# ADC-RDC-PHY.net
KiCad netlist of a schematic drawn in Altium Designer
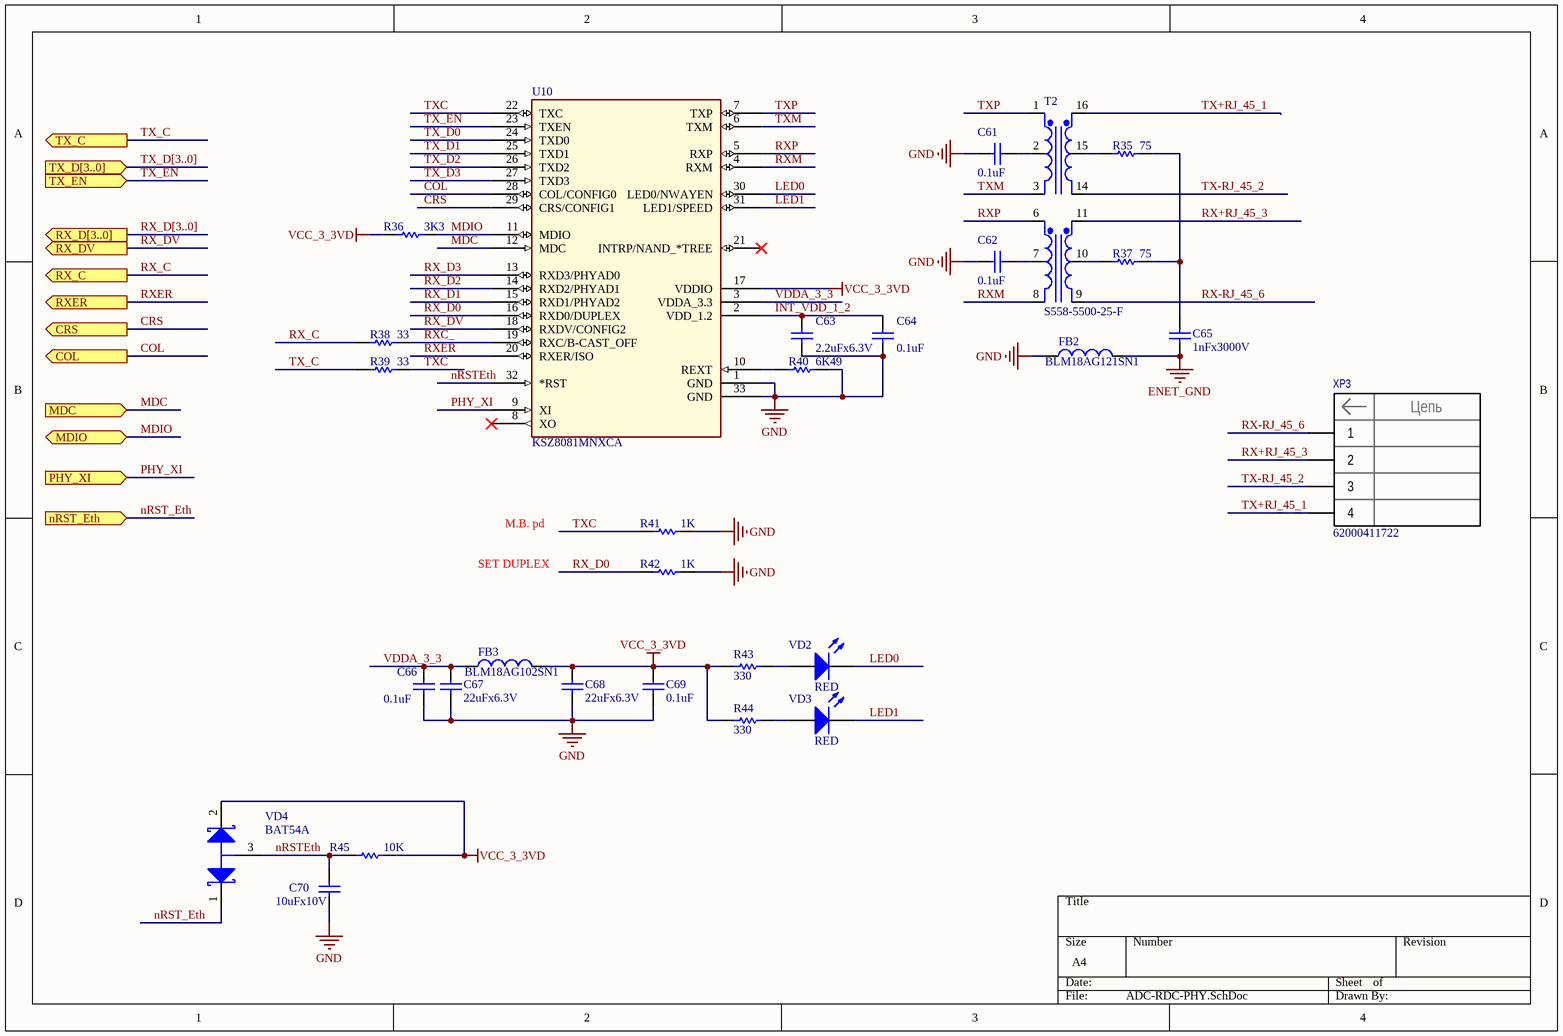
[diagram p0: ADC-RDC-PHY.SchDoc]

(export (version "E")
  (design (tool "Eeschema 10.0.6"))
  (components
    (comp (ref "C61")
      (value "0.1uF")
      (footprint "C0603")
      (description "Capacitor, 2pin")
      (libsource (lib "GC500EM2") (part "Cap"))
    )
    (comp (ref "C62")
      (value "0.1uF")
      (footprint "C0603")
      (description "Capacitor, 2pin")
      (libsource (lib "GC500EM2") (part "Cap"))
    )
    (comp (ref "C63")
      (value "2.2uFx6.3V")
      (footprint "C0603")
      (description "Capacitor, 2pin")
      (libsource (lib "GC500EM2") (part "Cap"))
    )
    (comp (ref "C64")
      (value "0.1uF")
      (footprint "C0603")
      (description "Capacitor, 2pin")
      (libsource (lib "GC500EM2") (part "Cap"))
    )
    (comp (ref "C65")
      (value "1nFx3000V")
      (footprint "C1808")
      (description "Capacitor, 2pin")
      (libsource (lib "GC500EM2") (part "Cap"))
    )
    (comp (ref "C66")
      (value "0.1uF")
      (footprint "C0603")
      (description "Capacitor, 2pin")
      (libsource (lib "GC500EM2") (part "Cap"))
    )
    (comp (ref "C67")
      (value "22uFx6.3V")
      (footprint "C0805")
      (description "Capacitor, 2pin")
      (libsource (lib "GC500EM2") (part "Cap"))
    )
    (comp (ref "C68")
      (value "22uFx6.3V")
      (footprint "C0805")
      (description "Capacitor, 2pin")
      (libsource (lib "GC500EM2") (part "Cap"))
    )
    (comp (ref "C69")
      (value "0.1uF")
      (footprint "C0603")
      (description "Capacitor, 2pin")
      (libsource (lib "GC500EM2") (part "Cap"))
    )
    (comp (ref "C70")
      (value "10uFx10V")
      (footprint "C0805")
      (description "Capacitor, 2pin")
      (libsource (lib "GC500EM2") (part "Cap"))
    )
    (comp (ref "FB2")
      (value "BLM18AG121SN1")
      (footprint "R0603")
      (description "Inductor, 2pin")
      (libsource (lib "GC500EM2") (part "Inductor"))
    )
    (comp (ref "FB3")
      (value "BLM18AG102SN1")
      (footprint "R0603")
      (description "Inductor, 2pin")
      (libsource (lib "GC500EM2") (part "Inductor"))
    )
    (comp (ref "R35")
      (value "75")
      (footprint "R0603")
      (description "Resistor, 2pin")
      (libsource (lib "GC500EM2") (part "RES"))
    )
    (comp (ref "R36")
      (value "3K3")
      (footprint "R0603")
      (description "Resistor, 2pin")
      (libsource (lib "GC500EM2") (part "RES"))
    )
    (comp (ref "R37")
      (value "75")
      (footprint "R0603")
      (description "Resistor, 2pin")
      (libsource (lib "GC500EM2") (part "RES"))
    )
    (comp (ref "R38")
      (value "33")
      (footprint "R0603")
      (description "Resistor, 2pin")
      (libsource (lib "GC500EM2") (part "RES"))
    )
    (comp (ref "R39")
      (value "33")
      (footprint "R0603")
      (description "Resistor, 2pin")
      (libsource (lib "GC500EM2") (part "RES"))
    )
    (comp (ref "R40")
      (value "6K49")
      (footprint "R0603")
      (description "Resistor, 2pin")
      (libsource (lib "GC500EM2") (part "RES"))
    )
    (comp (ref "R41")
      (value "1K")
      (footprint "R0603")
      (description "Resistor, 2pin")
      (libsource (lib "GC500EM2") (part "RES"))
    )
    (comp (ref "R42")
      (value "1K")
      (footprint "R0603")
      (description "Resistor, 2pin")
      (libsource (lib "GC500EM2") (part "RES"))
    )
    (comp (ref "R43")
      (value "330")
      (footprint "R0603")
      (description "Resistor, 2pin")
      (libsource (lib "GC500EM2") (part "RES"))
    )
    (comp (ref "R44")
      (value "330")
      (footprint "R0603")
      (description "Resistor, 2pin")
      (libsource (lib "GC500EM2") (part "RES"))
    )
    (comp (ref "R45")
      (value "10K")
      (footprint "R0603")
      (description "Resistor, 2pin")
      (libsource (lib "GC500EM2") (part "RES"))
    )
    (comp (ref "T2")
      (value "S558-5500-25-F")
      (footprint "N5")
      (description "Center-Tapped Transformer (Ideal)")
      (libsource (lib "GC500EM2") (part "TG110-E050N5"))
    )
    (comp (ref "U10")
      (value "KSZ8081MNXCA")
      (footprint "QFN32_L")
      (description "10BASE-T/100BASE-TX Physical Layer Transceiver")
      (libsource (lib "GC500EM2") (part "KSZ8081MNXCA"))
    )
    (comp (ref "VD2")
      (value "RED")
      (footprint "D0805")
      (description "Typical GaAs LED")
      (libsource (lib "GC500EM2") (part "LED"))
    )
    (comp (ref "VD3")
      (value "RED")
      (footprint "D0805")
      (description "Typical GaAs LED")
      (libsource (lib "GC500EM2") (part "LED"))
    )
    (comp (ref "VD4")
      (value "BAT54A")
      (footprint "SOT-23")
      (description "Schottky Barrier Double Diode")
      (libsource (lib "GC500EM2") (part "BAT54A"))
    )
    (comp (ref "XP3")
      (value "plug_62000411722_WR-WTB_4pin_horiz")
      (footprint "conP_WR-WTB_62000411722-4pin_P2000_100x76x48_L")
      (description "2.00mm Male Vertical Shrouded Header WR-WTB")
      (fields
        (field (name "COMPONENT_NAME") "62000411722")
        (field (name "MANUFACTURER") "\"Wurth Elektronik\"")
      )
      (libsource (lib "Electromechanics") (part "plug_62000411722_WR-WTB_4pin_horiz"))
    )
  )
  (nets
    (net (code "1") (name "/COL") (class "Default")
      (node (ref "U10") (pin "28") (pinfunction "COL/CONFIG0_28") (pintype "bidirectional"))
    )
    (net (code "2") (name "/CRS") (class "Default")
      (node (ref "U10") (pin "29") (pinfunction "CRS/CONFIG1_29") (pintype "bidirectional"))
    )
    (net (code "3") (name "/INT_VDD_1_2") (class "Default")
      (node (ref "C63") (pin "1") (pinfunction "1_1") (pintype "passive"))
      (node (ref "C64") (pin "2") (pinfunction "2_2") (pintype "passive"))
      (node (ref "U10") (pin "2") (pinfunction "VDD_1.2_2") (pintype "power_in"))
    )
    (net (code "4") (name "/LED0") (class "Default")
      (node (ref "U10") (pin "30") (pinfunction "LED0/NWAYEN_30") (pintype "bidirectional"))
      (node (ref "VD2") (pin "2") (pinfunction "K_2") (pintype "passive"))
    )
    (net (code "5") (name "/LED1") (class "Default")
      (node (ref "U10") (pin "31") (pinfunction "LED1/SPEED_31") (pintype "bidirectional"))
      (node (ref "VD3") (pin "2") (pinfunction "K_2") (pintype "passive"))
    )
    (net (code "6") (name "/MDC") (class "Default")
      (node (ref "U10") (pin "12") (pinfunction "MDC_12") (pintype "input"))
    )
    (net (code "7") (name "/MDIO") (class "Default")
      (node (ref "R36") (pin "2") (pinfunction "2_2") (pintype "passive"))
      (node (ref "U10") (pin "11") (pinfunction "MDIO_11") (pintype "bidirectional"))
    )
    (net (code "8") (name "/PHY_XI") (class "Default")
      (node (ref "U10") (pin "9") (pinfunction "XI_9") (pintype "input"))
    )
    (net (code "9") (name "/RX+RJ_45_3") (class "Default")
      (node (ref "T2") (pin "11") (pinfunction "Pri2+_11") (pintype "passive"))
      (node (ref "XP3") (pin "2") (pinfunction "2_2") (pintype "passive"))
    )
    (net (code "10") (name "/RX-RJ_45_6") (class "Default")
      (node (ref "T2") (pin "9") (pinfunction "Pri2-_9") (pintype "passive"))
      (node (ref "XP3") (pin "1") (pinfunction "1_1") (pintype "passive"))
    )
    (net (code "11") (name "/RXC_") (class "Default")
      (node (ref "R38") (pin "2") (pinfunction "2_2") (pintype "passive"))
      (node (ref "U10") (pin "19") (pinfunction "RXC/B-CAST_OFF_19") (pintype "bidirectional"))
    )
    (net (code "12") (name "/RXER") (class "Default")
      (node (ref "U10") (pin "20") (pinfunction "RXER/ISO_20") (pintype "bidirectional"))
    )
    (net (code "13") (name "/RXM") (class "Default")
      (node (ref "T2") (pin "8") (pinfunction "Sec2-_8") (pintype "passive"))
      (node (ref "U10") (pin "4") (pinfunction "RXM_4") (pintype "bidirectional"))
    )
    (net (code "14") (name "/RXP") (class "Default")
      (node (ref "T2") (pin "6") (pinfunction "Sec2+_6") (pintype "passive"))
      (node (ref "U10") (pin "5") (pinfunction "RXP_5") (pintype "bidirectional"))
    )
    (net (code "15") (name "/RX_C") (class "Default")
      (node (ref "R38") (pin "1") (pinfunction "1_1") (pintype "passive"))
    )
    (net (code "16") (name "/RX_D0") (class "Default")
      (node (ref "R42") (pin "1") (pinfunction "1_1") (pintype "passive"))
      (node (ref "U10") (pin "16") (pinfunction "RXD0/DUPLEX_16") (pintype "bidirectional"))
    )
    (net (code "17") (name "/RX_D1") (class "Default")
      (node (ref "U10") (pin "15") (pinfunction "RXD1/PHYAD2_15") (pintype "bidirectional"))
    )
    (net (code "18") (name "/RX_D2") (class "Default")
      (node (ref "U10") (pin "14") (pinfunction "RXD2/PHYAD1_14") (pintype "bidirectional"))
    )
    (net (code "19") (name "/RX_D3") (class "Default")
      (node (ref "U10") (pin "13") (pinfunction "RXD3/PHYAD0_13") (pintype "bidirectional"))
    )
    (net (code "20") (name "/RX_DV") (class "Default")
      (node (ref "U10") (pin "18") (pinfunction "RXDV/CONFIG2_18") (pintype "bidirectional"))
    )
    (net (code "22") (name "/TX+RJ_45_1") (class "Default")
      (node (ref "T2") (pin "16") (pinfunction "Pri1+_16") (pintype "passive"))
      (node (ref "XP3") (pin "4") (pinfunction "4_4") (pintype "passive"))
    )
    (net (code "23") (name "/TX-RJ_45_2") (class "Default")
      (node (ref "T2") (pin "14") (pinfunction "Pri1-_14") (pintype "passive"))
      (node (ref "XP3") (pin "3") (pinfunction "3_3") (pintype "passive"))
    )
    (net (code "24") (name "/TXC") (class "Default")
      (node (ref "R39") (pin "2") (pinfunction "2_2") (pintype "passive"))
      (node (ref "R41") (pin "1") (pinfunction "1_1") (pintype "passive"))
      (node (ref "U10") (pin "22") (pinfunction "TXC_22") (pintype "bidirectional"))
    )
    (net (code "25") (name "/TXM") (class "Default")
      (node (ref "T2") (pin "3") (pinfunction "Sec1-_3") (pintype "passive"))
      (node (ref "U10") (pin "6") (pinfunction "TXM_6") (pintype "bidirectional"))
    )
    (net (code "26") (name "/TXP") (class "Default")
      (node (ref "T2") (pin "1") (pinfunction "Sec1+_1") (pintype "passive"))
      (node (ref "U10") (pin "7") (pinfunction "TXP_7") (pintype "bidirectional"))
    )
    (net (code "27") (name "/TX_C") (class "Default")
      (node (ref "R39") (pin "1") (pinfunction "1_1") (pintype "passive"))
    )
    (net (code "28") (name "/TX_D0") (class "Default")
      (node (ref "U10") (pin "24") (pinfunction "TXD0_24") (pintype "input"))
    )
    (net (code "29") (name "/TX_D1") (class "Default")
      (node (ref "U10") (pin "25") (pinfunction "TXD1_25") (pintype "input"))
    )
    (net (code "30") (name "/TX_D2") (class "Default")
      (node (ref "U10") (pin "26") (pinfunction "TXD2_26") (pintype "input"))
    )
    (net (code "31") (name "/TX_D3") (class "Default")
      (node (ref "U10") (pin "27") (pinfunction "TXD3_27") (pintype "input"))
    )
    (net (code "33") (name "/TX_EN") (class "Default")
      (node (ref "U10") (pin "23") (pinfunction "TXEN_23") (pintype "input"))
    )
    (net (code "34") (name "/VDDA_3_3") (class "Default")
      (node (ref "C66") (pin "2") (pinfunction "2_2") (pintype "passive"))
      (node (ref "C67") (pin "2") (pinfunction "2_2") (pintype "passive"))
      (node (ref "FB3") (pin "2") (pinfunction "2_2") (pintype "passive"))
      (node (ref "U10") (pin "3") (pinfunction "VDDA_3.3_3") (pintype "power_in"))
    )
    (net (code "35") (name "/nRSTEth") (class "Default")
      (node (ref "C70") (pin "1") (pinfunction "1_1") (pintype "passive"))
      (node (ref "R45") (pin "1") (pinfunction "1_1") (pintype "passive"))
      (node (ref "U10") (pin "32") (pinfunction "*RST_32") (pintype "input"))
      (node (ref "VD4") (pin "3") (pinfunction "K_3") (pintype "passive"))
    )
    (net (code "36") (name "/nRST_Eth") (class "Default")
      (node (ref "VD4") (pin "1") (pinfunction "A1_1") (pintype "passive"))
    )
    (net (code "37") (name "ENET_GND") (class "Default")
      (node (ref "C65") (pin "2") (pinfunction "2_2") (pintype "passive"))
      (node (ref "FB2") (pin "1") (pinfunction "1_1") (pintype "passive"))
    )
    (net (code "38") (name "GND") (class "Default")
      (node (ref "C61") (pin "2") (pinfunction "2_2") (pintype "passive"))
      (node (ref "C62") (pin "2") (pinfunction "2_2") (pintype "passive"))
      (node (ref "C63") (pin "2") (pinfunction "2_2") (pintype "passive"))
      (node (ref "C64") (pin "1") (pinfunction "1_1") (pintype "passive"))
      (node (ref "C66") (pin "1") (pinfunction "1_1") (pintype "passive"))
      (node (ref "C67") (pin "1") (pinfunction "1_1") (pintype "passive"))
      (node (ref "C68") (pin "1") (pinfunction "1_1") (pintype "passive"))
      (node (ref "C69") (pin "1") (pinfunction "1_1") (pintype "passive"))
      (node (ref "C70") (pin "2") (pinfunction "2_2") (pintype "passive"))
      (node (ref "FB2") (pin "2") (pinfunction "2_2") (pintype "passive"))
      (node (ref "R40") (pin "2") (pinfunction "2_2") (pintype "passive"))
      (node (ref "R41") (pin "2") (pinfunction "2_2") (pintype "passive"))
      (node (ref "R42") (pin "2") (pinfunction "2_2") (pintype "passive"))
      (node (ref "U10") (pin "1") (pinfunction "GND_1") (pintype "power_in"))
      (node (ref "U10") (pin "33") (pinfunction "GND_33") (pintype "passive"))
    )
    (net (code "39") (name "Net-(C65-Pad1)") (class "Default")
      (node (ref "C65") (pin "1") (pinfunction "1_1") (pintype "passive"))
      (node (ref "R35") (pin "2") (pinfunction "2_2") (pintype "passive"))
      (node (ref "R37") (pin "2") (pinfunction "2_2") (pintype "passive"))
    )
    (net (code "40") (name "Net-(T2-Pri1CT)") (class "Default")
      (node (ref "R35") (pin "1") (pinfunction "1_1") (pintype "passive"))
      (node (ref "T2") (pin "15") (pinfunction "Pri1CT_15") (pintype "passive"))
    )
    (net (code "41") (name "Net-(T2-Pri2CT)") (class "Default")
      (node (ref "R37") (pin "1") (pinfunction "1_1") (pintype "passive"))
      (node (ref "T2") (pin "10") (pinfunction "Pri2CT_10") (pintype "passive"))
    )
    (net (code "42") (name "Net-(T2-Sec1CT)") (class "Default")
      (node (ref "C61") (pin "1") (pinfunction "1_1") (pintype "passive"))
      (node (ref "T2") (pin "2") (pinfunction "Sec1CT_2") (pintype "passive"))
    )
    (net (code "43") (name "Net-(T2-Sec2CT)") (class "Default")
      (node (ref "C62") (pin "1") (pinfunction "1_1") (pintype "passive"))
      (node (ref "T2") (pin "7") (pinfunction "Sec2CT_7") (pintype "passive"))
    )
    (net (code "44") (name "Net-(U10-REXT)") (class "Default")
      (node (ref "R40") (pin "1") (pinfunction "1_1") (pintype "passive"))
      (node (ref "U10") (pin "10") (pinfunction "REXT_10") (pintype "input"))
    )
    (net (code "45") (name "Net-(VD2-A)") (class "Default")
      (node (ref "R43") (pin "1") (pinfunction "1_1") (pintype "passive"))
      (node (ref "VD2") (pin "1") (pinfunction "A_1") (pintype "passive"))
    )
    (net (code "46") (name "Net-(VD3-A)") (class "Default")
      (node (ref "R44") (pin "1") (pinfunction "1_1") (pintype "passive"))
      (node (ref "VD3") (pin "1") (pinfunction "A_1") (pintype "passive"))
    )
    (net (code "47") (name "VCC_3_3VD") (class "Default")
      (node (ref "C68") (pin "2") (pinfunction "2_2") (pintype "passive"))
      (node (ref "C69") (pin "2") (pinfunction "2_2") (pintype "passive"))
      (node (ref "FB3") (pin "1") (pinfunction "1_1") (pintype "passive"))
      (node (ref "R36") (pin "1") (pinfunction "1_1") (pintype "passive"))
      (node (ref "R43") (pin "2") (pinfunction "2_2") (pintype "passive"))
      (node (ref "R44") (pin "2") (pinfunction "2_2") (pintype "passive"))
      (node (ref "R45") (pin "2") (pinfunction "2_2") (pintype "passive"))
      (node (ref "U10") (pin "17") (pinfunction "VDDIO_17") (pintype "power_in"))
      (node (ref "VD4") (pin "2") (pinfunction "A2_2") (pintype "passive"))
    )
    (net (code "48") (name "unconnected-(U10-INTRP{slash}NAND_*TREE-Pad21)") (class "Default")
      (node (ref "U10") (pin "21") (pinfunction "INTRP/NAND_*TREE_21") (pintype "bidirectional+no_connect"))
    )
    (net (code "49") (name "unconnected-(U10-XO-Pad8)") (class "Default")
      (node (ref "U10") (pin "8") (pinfunction "XO_8") (pintype "output+no_connect"))
    )
  )
)
